# temp-stellwerk-laser-4.net
KiCad netlist of a schematic drawn in EAGLE
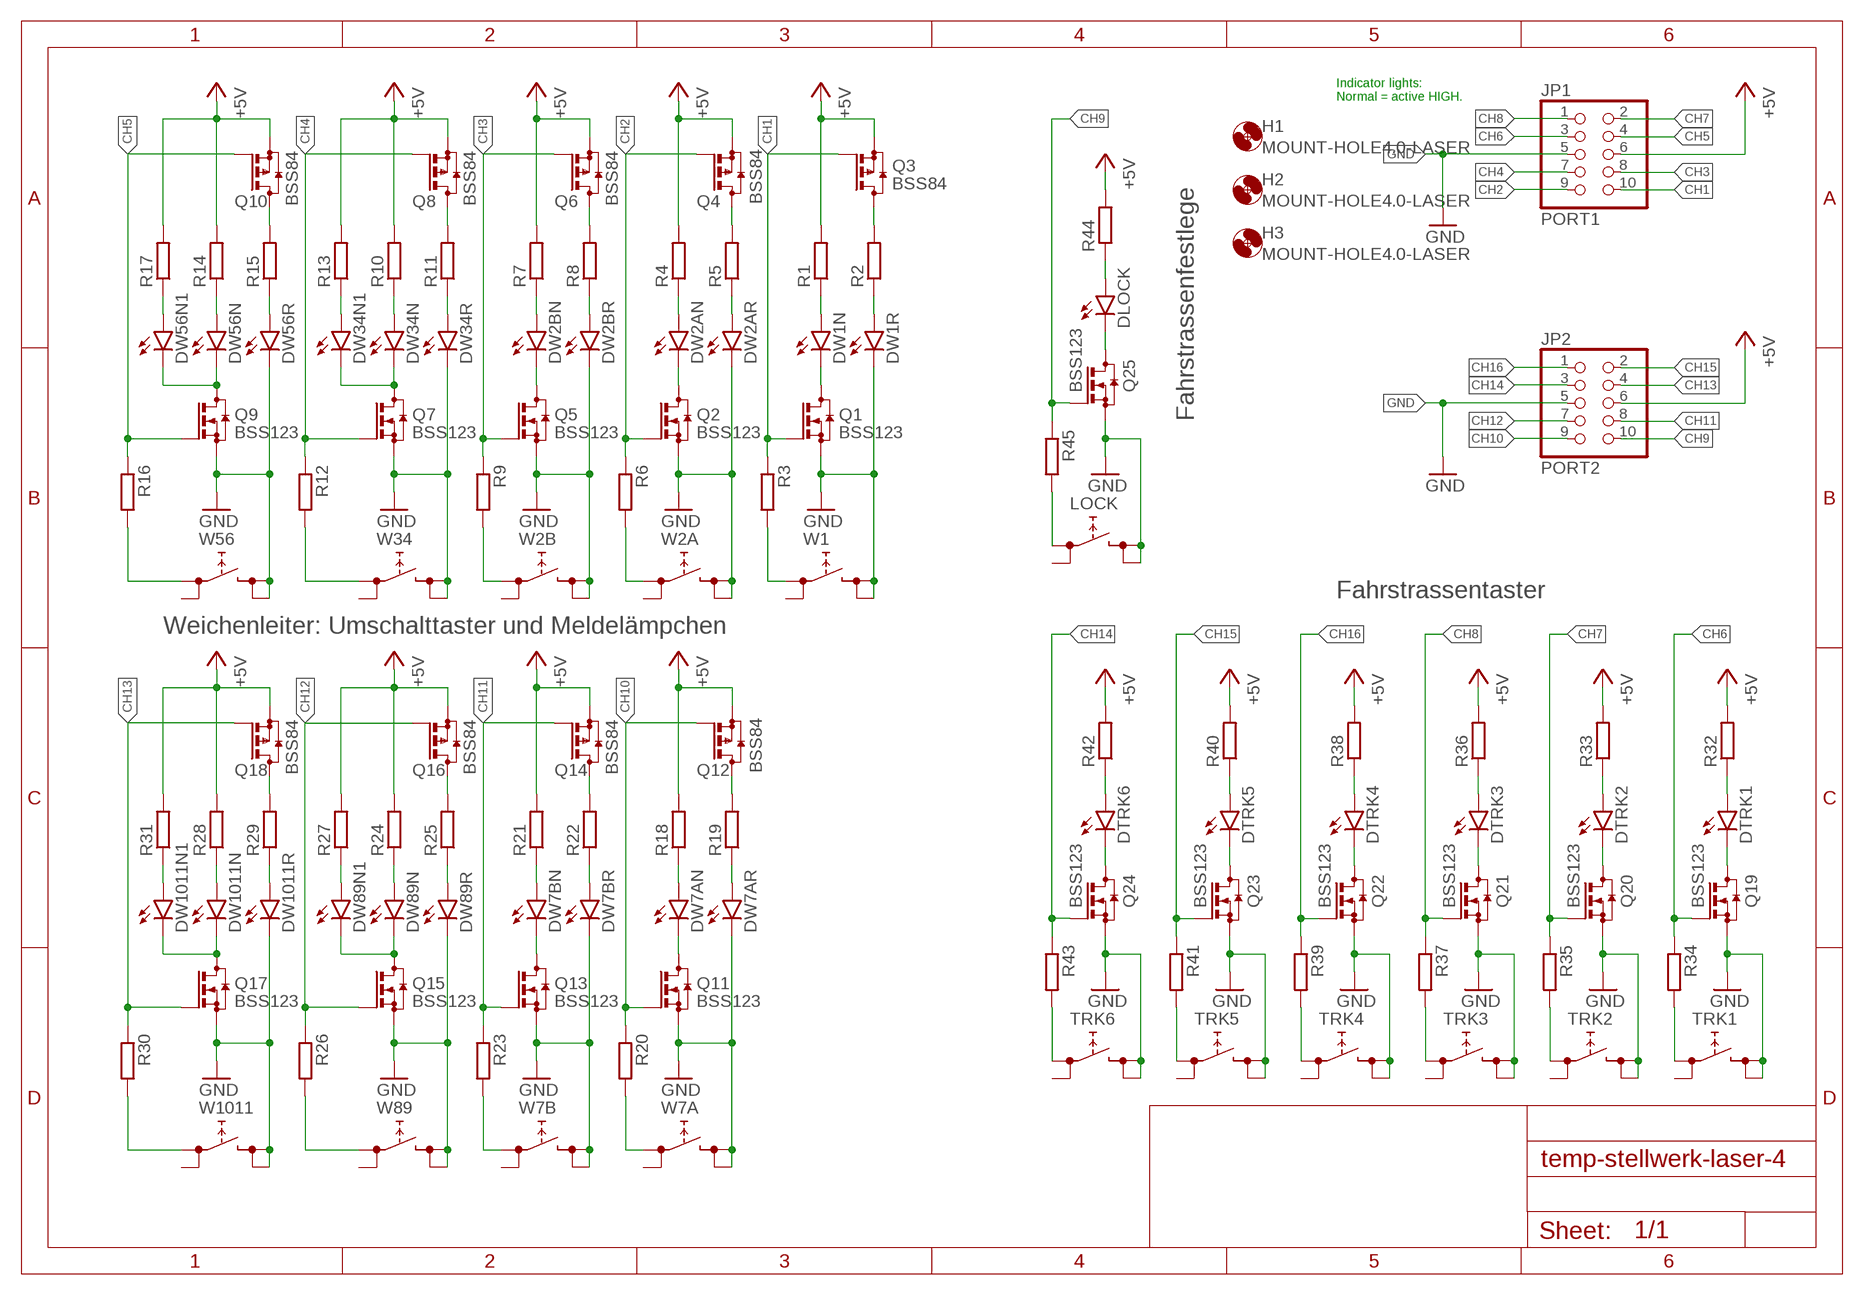
[diagram p0: schematic, sheet 1]

(export (version "E")
  (design (tool "Eeschema 10.0.6"))
  (components
    (comp (ref "DLOCK")
      (value "LEDCHIPLED_0805")
      (footprint "eagle-import:CHIPLED_0805")
      (libsource (lib "eagle-import") (part "LEDCHIPLED_0805"))
    )
    (comp (ref "DTRK1")
      (value "LEDCHIPLED_0805")
      (footprint "eagle-import:CHIPLED_0805")
      (libsource (lib "eagle-import") (part "LEDCHIPLED_0805"))
    )
    (comp (ref "DTRK2")
      (value "LEDCHIPLED_0805")
      (footprint "eagle-import:CHIPLED_0805")
      (libsource (lib "eagle-import") (part "LEDCHIPLED_0805"))
    )
    (comp (ref "DTRK3")
      (value "LEDCHIPLED_0805")
      (footprint "eagle-import:CHIPLED_0805")
      (libsource (lib "eagle-import") (part "LEDCHIPLED_0805"))
    )
    (comp (ref "DTRK4")
      (value "LEDCHIPLED_0805")
      (footprint "eagle-import:CHIPLED_0805")
      (libsource (lib "eagle-import") (part "LEDCHIPLED_0805"))
    )
    (comp (ref "DTRK5")
      (value "LEDCHIPLED_0805")
      (footprint "eagle-import:CHIPLED_0805")
      (libsource (lib "eagle-import") (part "LEDCHIPLED_0805"))
    )
    (comp (ref "DTRK6")
      (value "LEDCHIPLED_0805")
      (footprint "eagle-import:CHIPLED_0805")
      (libsource (lib "eagle-import") (part "LEDCHIPLED_0805"))
    )
    (comp (ref "DW1N")
      (value "LEDCHIPLED_0603")
      (footprint "eagle-import:CHIPLED_0603")
      (libsource (lib "eagle-import") (part "LEDCHIPLED_0603"))
    )
    (comp (ref "DW1R")
      (value "LEDCHIPLED_0603")
      (footprint "eagle-import:CHIPLED_0603")
      (libsource (lib "eagle-import") (part "LEDCHIPLED_0603"))
    )
    (comp (ref "DW2AN")
      (value "LEDCHIPLED_0603")
      (footprint "eagle-import:CHIPLED_0603")
      (libsource (lib "eagle-import") (part "LEDCHIPLED_0603"))
    )
    (comp (ref "DW2AR")
      (value "LEDCHIPLED_0603")
      (footprint "eagle-import:CHIPLED_0603")
      (libsource (lib "eagle-import") (part "LEDCHIPLED_0603"))
    )
    (comp (ref "DW2BN")
      (value "LEDCHIPLED_0805")
      (footprint "eagle-import:CHIPLED_0805")
      (libsource (lib "eagle-import") (part "LEDCHIPLED_0805"))
    )
    (comp (ref "DW2BR")
      (value "LEDCHIPLED_0805")
      (footprint "eagle-import:CHIPLED_0805")
      (libsource (lib "eagle-import") (part "LEDCHIPLED_0805"))
    )
    (comp (ref "DW7AN")
      (value "LEDCHIPLED_0603")
      (footprint "eagle-import:CHIPLED_0603")
      (libsource (lib "eagle-import") (part "LEDCHIPLED_0603"))
    )
    (comp (ref "DW7AR")
      (value "LEDCHIPLED_0603")
      (footprint "eagle-import:CHIPLED_0603")
      (libsource (lib "eagle-import") (part "LEDCHIPLED_0603"))
    )
    (comp (ref "DW7BN")
      (value "LEDCHIPLED_0805")
      (footprint "eagle-import:CHIPLED_0805")
      (libsource (lib "eagle-import") (part "LEDCHIPLED_0805"))
    )
    (comp (ref "DW7BR")
      (value "LEDCHIPLED_0805")
      (footprint "eagle-import:CHIPLED_0805")
      (libsource (lib "eagle-import") (part "LEDCHIPLED_0805"))
    )
    (comp (ref "DW34N")
      (value "LEDCHIPLED_0805")
      (footprint "eagle-import:CHIPLED_0805")
      (libsource (lib "eagle-import") (part "LEDCHIPLED_0805"))
    )
    (comp (ref "DW34N1")
      (value "LEDCHIPLED_0805")
      (footprint "eagle-import:CHIPLED_0805")
      (libsource (lib "eagle-import") (part "LEDCHIPLED_0805"))
    )
    (comp (ref "DW34R")
      (value "LEDCHIPLED_0805")
      (footprint "eagle-import:CHIPLED_0805")
      (libsource (lib "eagle-import") (part "LEDCHIPLED_0805"))
    )
    (comp (ref "DW56N")
      (value "LEDCHIPLED_0805")
      (footprint "eagle-import:CHIPLED_0805")
      (libsource (lib "eagle-import") (part "LEDCHIPLED_0805"))
    )
    (comp (ref "DW56N1")
      (value "LEDCHIPLED_0805")
      (footprint "eagle-import:CHIPLED_0805")
      (libsource (lib "eagle-import") (part "LEDCHIPLED_0805"))
    )
    (comp (ref "DW56R")
      (value "LEDCHIPLED_0805")
      (footprint "eagle-import:CHIPLED_0805")
      (libsource (lib "eagle-import") (part "LEDCHIPLED_0805"))
    )
    (comp (ref "DW89N")
      (value "LEDCHIPLED_0805")
      (footprint "eagle-import:CHIPLED_0805")
      (libsource (lib "eagle-import") (part "LEDCHIPLED_0805"))
    )
    (comp (ref "DW89N1")
      (value "LEDCHIPLED_0805")
      (footprint "eagle-import:CHIPLED_0805")
      (libsource (lib "eagle-import") (part "LEDCHIPLED_0805"))
    )
    (comp (ref "DW89R")
      (value "LEDCHIPLED_0805")
      (footprint "eagle-import:CHIPLED_0805")
      (libsource (lib "eagle-import") (part "LEDCHIPLED_0805"))
    )
    (comp (ref "DW1011N")
      (value "LEDCHIPLED_0805")
      (footprint "eagle-import:CHIPLED_0805")
      (libsource (lib "eagle-import") (part "LEDCHIPLED_0805"))
    )
    (comp (ref "DW1011N1")
      (value "LEDCHIPLED_0805")
      (footprint "eagle-import:CHIPLED_0805")
      (libsource (lib "eagle-import") (part "LEDCHIPLED_0805"))
    )
    (comp (ref "DW1011R")
      (value "LEDCHIPLED_0805")
      (footprint "eagle-import:CHIPLED_0805")
      (libsource (lib "eagle-import") (part "LEDCHIPLED_0805"))
    )
    (comp (ref "H1")
      (value "MOUNT-HOLE4.0-LASER")
      (footprint "eagle-import:MOUNT-HOLE-3.2-4.0-LASER")
      (libsource (lib "eagle-import") (part "MOUNT-HOLE4.0-LASER"))
    )
    (comp (ref "H2")
      (value "MOUNT-HOLE4.0-LASER")
      (footprint "eagle-import:MOUNT-HOLE-3.2-4.0-LASER")
      (libsource (lib "eagle-import") (part "MOUNT-HOLE4.0-LASER"))
    )
    (comp (ref "H3")
      (value "MOUNT-HOLE4.0-LASER")
      (footprint "eagle-import:MOUNT-HOLE-3.2-4.0-LASER")
      (libsource (lib "eagle-import") (part "MOUNT-HOLE4.0-LASER"))
    )
    (comp (ref "JP1")
      (value "PORT1")
      (footprint "eagle-import:CON10M")
      (libsource (lib "eagle-import") (part "PINHD-2X5CN"))
    )
    (comp (ref "JP2")
      (value "PORT2")
      (footprint "eagle-import:CON10M")
      (libsource (lib "eagle-import") (part "PINHD-2X5CN"))
    )
    (comp (ref "LOCK")
      (value "LOCK")
      (footprint "eagle-import:TACTSW-6X6-LASER")
      (libsource (lib "eagle-import") (part "TACTSW-6X6S"))
    )
    (comp (ref "Q1")
      (value "BSS123")
      (footprint "eagle-import:SOT23-NCH")
      (libsource (lib "eagle-import") (part "BSS123"))
    )
    (comp (ref "Q2")
      (value "BSS123")
      (footprint "eagle-import:SOT23-NCH")
      (libsource (lib "eagle-import") (part "BSS123"))
    )
    (comp (ref "Q3")
      (value "BSS84")
      (footprint "eagle-import:SOT23")
      (libsource (lib "eagle-import") (part "BSS84"))
    )
    (comp (ref "Q4")
      (value "BSS84")
      (footprint "eagle-import:SOT23")
      (libsource (lib "eagle-import") (part "BSS84"))
    )
    (comp (ref "Q5")
      (value "BSS123")
      (footprint "eagle-import:SOT23-NCH")
      (libsource (lib "eagle-import") (part "BSS123"))
    )
    (comp (ref "Q6")
      (value "BSS84")
      (footprint "eagle-import:SOT23")
      (libsource (lib "eagle-import") (part "BSS84"))
    )
    (comp (ref "Q7")
      (value "BSS123")
      (footprint "eagle-import:SOT23-NCH")
      (libsource (lib "eagle-import") (part "BSS123"))
    )
    (comp (ref "Q8")
      (value "BSS84")
      (footprint "eagle-import:SOT23")
      (libsource (lib "eagle-import") (part "BSS84"))
    )
    (comp (ref "Q9")
      (value "BSS123")
      (footprint "eagle-import:SOT23-NCH")
      (libsource (lib "eagle-import") (part "BSS123"))
    )
    (comp (ref "Q10")
      (value "BSS84")
      (footprint "eagle-import:SOT23")
      (libsource (lib "eagle-import") (part "BSS84"))
    )
    (comp (ref "Q11")
      (value "BSS123")
      (footprint "eagle-import:SOT23-NCH")
      (libsource (lib "eagle-import") (part "BSS123"))
    )
    (comp (ref "Q12")
      (value "BSS84")
      (footprint "eagle-import:SOT23")
      (libsource (lib "eagle-import") (part "BSS84"))
    )
    (comp (ref "Q13")
      (value "BSS123")
      (footprint "eagle-import:SOT23-NCH")
      (libsource (lib "eagle-import") (part "BSS123"))
    )
    (comp (ref "Q14")
      (value "BSS84")
      (footprint "eagle-import:SOT23")
      (libsource (lib "eagle-import") (part "BSS84"))
    )
    (comp (ref "Q15")
      (value "BSS123")
      (footprint "eagle-import:SOT23-NCH")
      (libsource (lib "eagle-import") (part "BSS123"))
    )
    (comp (ref "Q16")
      (value "BSS84")
      (footprint "eagle-import:SOT23")
      (libsource (lib "eagle-import") (part "BSS84"))
    )
    (comp (ref "Q17")
      (value "BSS123")
      (footprint "eagle-import:SOT23-NCH")
      (libsource (lib "eagle-import") (part "BSS123"))
    )
    (comp (ref "Q18")
      (value "BSS84")
      (footprint "eagle-import:SOT23")
      (libsource (lib "eagle-import") (part "BSS84"))
    )
    (comp (ref "Q19")
      (value "BSS123")
      (footprint "eagle-import:SOT23-NCH")
      (libsource (lib "eagle-import") (part "BSS123"))
    )
    (comp (ref "Q20")
      (value "BSS123")
      (footprint "eagle-import:SOT23-NCH")
      (libsource (lib "eagle-import") (part "BSS123"))
    )
    (comp (ref "Q21")
      (value "BSS123")
      (footprint "eagle-import:SOT23-NCH")
      (libsource (lib "eagle-import") (part "BSS123"))
    )
    (comp (ref "Q22")
      (value "BSS123")
      (footprint "eagle-import:SOT23-NCH")
      (libsource (lib "eagle-import") (part "BSS123"))
    )
    (comp (ref "Q23")
      (value "BSS123")
      (footprint "eagle-import:SOT23-NCH")
      (libsource (lib "eagle-import") (part "BSS123"))
    )
    (comp (ref "Q24")
      (value "BSS123")
      (footprint "eagle-import:SOT23-NCH")
      (libsource (lib "eagle-import") (part "BSS123"))
    )
    (comp (ref "Q25")
      (value "BSS123")
      (footprint "eagle-import:SOT23-NCH")
      (libsource (lib "eagle-import") (part "BSS123"))
    )
    (comp (ref "R1")
      (value "R-EU_R0805")
      (footprint "eagle-import:R0805")
      (libsource (lib "eagle-import") (part "R-EU_R0805"))
    )
    (comp (ref "R2")
      (value "R-EU_R0805")
      (footprint "eagle-import:R0805")
      (libsource (lib "eagle-import") (part "R-EU_R0805"))
    )
    (comp (ref "R3")
      (value "R-EU_R0805")
      (footprint "eagle-import:R0805")
      (libsource (lib "eagle-import") (part "R-EU_R0805"))
    )
    (comp (ref "R4")
      (value "R-EU_R0805")
      (footprint "eagle-import:R0805")
      (libsource (lib "eagle-import") (part "R-EU_R0805"))
    )
    (comp (ref "R5")
      (value "R-EU_R0805")
      (footprint "eagle-import:R0805")
      (libsource (lib "eagle-import") (part "R-EU_R0805"))
    )
    (comp (ref "R6")
      (value "R-EU_R0805")
      (footprint "eagle-import:R0805")
      (libsource (lib "eagle-import") (part "R-EU_R0805"))
    )
    (comp (ref "R7")
      (value "R-EU_R0805")
      (footprint "eagle-import:R0805")
      (libsource (lib "eagle-import") (part "R-EU_R0805"))
    )
    (comp (ref "R8")
      (value "R-EU_R0805")
      (footprint "eagle-import:R0805")
      (libsource (lib "eagle-import") (part "R-EU_R0805"))
    )
    (comp (ref "R9")
      (value "R-EU_R0805")
      (footprint "eagle-import:R0805")
      (libsource (lib "eagle-import") (part "R-EU_R0805"))
    )
    (comp (ref "R10")
      (value "R-EU_R0805")
      (footprint "eagle-import:R0805")
      (libsource (lib "eagle-import") (part "R-EU_R0805"))
    )
    (comp (ref "R11")
      (value "R-EU_R0805")
      (footprint "eagle-import:R0805")
      (libsource (lib "eagle-import") (part "R-EU_R0805"))
    )
    (comp (ref "R12")
      (value "R-EU_R0805")
      (footprint "eagle-import:R0805")
      (libsource (lib "eagle-import") (part "R-EU_R0805"))
    )
    (comp (ref "R13")
      (value "R-EU_R0805")
      (footprint "eagle-import:R0805")
      (libsource (lib "eagle-import") (part "R-EU_R0805"))
    )
    (comp (ref "R14")
      (value "R-EU_R0805")
      (footprint "eagle-import:R0805")
      (libsource (lib "eagle-import") (part "R-EU_R0805"))
    )
    (comp (ref "R15")
      (value "R-EU_R0805")
      (footprint "eagle-import:R0805")
      (libsource (lib "eagle-import") (part "R-EU_R0805"))
    )
    (comp (ref "R16")
      (value "R-EU_R0805")
      (footprint "eagle-import:R0805")
      (libsource (lib "eagle-import") (part "R-EU_R0805"))
    )
    (comp (ref "R17")
      (value "R-EU_R0805")
      (footprint "eagle-import:R0805")
      (libsource (lib "eagle-import") (part "R-EU_R0805"))
    )
    (comp (ref "R18")
      (value "R-EU_R0805")
      (footprint "eagle-import:R0805")
      (libsource (lib "eagle-import") (part "R-EU_R0805"))
    )
    (comp (ref "R19")
      (value "R-EU_R0805")
      (footprint "eagle-import:R0805")
      (libsource (lib "eagle-import") (part "R-EU_R0805"))
    )
    (comp (ref "R20")
      (value "R-EU_R0805")
      (footprint "eagle-import:R0805")
      (libsource (lib "eagle-import") (part "R-EU_R0805"))
    )
    (comp (ref "R21")
      (value "R-EU_R0805")
      (footprint "eagle-import:R0805")
      (libsource (lib "eagle-import") (part "R-EU_R0805"))
    )
    (comp (ref "R22")
      (value "R-EU_R0805")
      (footprint "eagle-import:R0805")
      (libsource (lib "eagle-import") (part "R-EU_R0805"))
    )
    (comp (ref "R23")
      (value "R-EU_R0805")
      (footprint "eagle-import:R0805")
      (libsource (lib "eagle-import") (part "R-EU_R0805"))
    )
    (comp (ref "R24")
      (value "R-EU_R0805")
      (footprint "eagle-import:R0805")
      (libsource (lib "eagle-import") (part "R-EU_R0805"))
    )
    (comp (ref "R25")
      (value "R-EU_R0805")
      (footprint "eagle-import:R0805")
      (libsource (lib "eagle-import") (part "R-EU_R0805"))
    )
    (comp (ref "R26")
      (value "R-EU_R0805")
      (footprint "eagle-import:R0805")
      (libsource (lib "eagle-import") (part "R-EU_R0805"))
    )
    (comp (ref "R27")
      (value "R-EU_R0805")
      (footprint "eagle-import:R0805")
      (libsource (lib "eagle-import") (part "R-EU_R0805"))
    )
    (comp (ref "R28")
      (value "R-EU_R0805")
      (footprint "eagle-import:R0805")
      (libsource (lib "eagle-import") (part "R-EU_R0805"))
    )
    (comp (ref "R29")
      (value "R-EU_R0805")
      (footprint "eagle-import:R0805")
      (libsource (lib "eagle-import") (part "R-EU_R0805"))
    )
    (comp (ref "R30")
      (value "R-EU_R0805")
      (footprint "eagle-import:R0805")
      (libsource (lib "eagle-import") (part "R-EU_R0805"))
    )
    (comp (ref "R31")
      (value "R-EU_R0805")
      (footprint "eagle-import:R0805")
      (libsource (lib "eagle-import") (part "R-EU_R0805"))
    )
    (comp (ref "R32")
      (value "R-EU_R0805")
      (footprint "eagle-import:R0805")
      (libsource (lib "eagle-import") (part "R-EU_R0805"))
    )
    (comp (ref "R33")
      (value "R-EU_R0805")
      (footprint "eagle-import:R0805")
      (libsource (lib "eagle-import") (part "R-EU_R0805"))
    )
    (comp (ref "R34")
      (value "R-EU_R0805")
      (footprint "eagle-import:R0805")
      (libsource (lib "eagle-import") (part "R-EU_R0805"))
    )
    (comp (ref "R35")
      (value "R-EU_R0805")
      (footprint "eagle-import:R0805")
      (libsource (lib "eagle-import") (part "R-EU_R0805"))
    )
    (comp (ref "R36")
      (value "R-EU_R0805")
      (footprint "eagle-import:R0805")
      (libsource (lib "eagle-import") (part "R-EU_R0805"))
    )
    (comp (ref "R37")
      (value "R-EU_R0805")
      (footprint "eagle-import:R0805")
      (libsource (lib "eagle-import") (part "R-EU_R0805"))
    )
    (comp (ref "R38")
      (value "R-EU_R0805")
      (footprint "eagle-import:R0805")
      (libsource (lib "eagle-import") (part "R-EU_R0805"))
    )
    (comp (ref "R39")
      (value "R-EU_R0805")
      (footprint "eagle-import:R0805")
      (libsource (lib "eagle-import") (part "R-EU_R0805"))
    )
    (comp (ref "R40")
      (value "R-EU_R0805")
      (footprint "eagle-import:R0805")
      (libsource (lib "eagle-import") (part "R-EU_R0805"))
    )
    (comp (ref "R41")
      (value "R-EU_R0805")
      (footprint "eagle-import:R0805")
      (libsource (lib "eagle-import") (part "R-EU_R0805"))
    )
    (comp (ref "R42")
      (value "R-EU_R0805")
      (footprint "eagle-import:R0805")
      (libsource (lib "eagle-import") (part "R-EU_R0805"))
    )
    (comp (ref "R43")
      (value "R-EU_R0805")
      (footprint "eagle-import:R0805")
      (libsource (lib "eagle-import") (part "R-EU_R0805"))
    )
    (comp (ref "R44")
      (value "R-EU_R0805")
      (footprint "eagle-import:R0805")
      (libsource (lib "eagle-import") (part "R-EU_R0805"))
    )
    (comp (ref "R45")
      (value "R-EU_R0805")
      (footprint "eagle-import:R0805")
      (libsource (lib "eagle-import") (part "R-EU_R0805"))
    )
    (comp (ref "TRK1")
      (value "TACTSW-6X6S")
      (footprint "eagle-import:TACTSW-6X6-LASER")
      (libsource (lib "eagle-import") (part "TACTSW-6X6S"))
    )
    (comp (ref "TRK2")
      (value "TACTSW-6X6S")
      (footprint "eagle-import:TACTSW-6X6-LASER")
      (libsource (lib "eagle-import") (part "TACTSW-6X6S"))
    )
    (comp (ref "TRK3")
      (value "TACTSW-6X6S")
      (footprint "eagle-import:TACTSW-6X6-LASER")
      (libsource (lib "eagle-import") (part "TACTSW-6X6S"))
    )
    (comp (ref "TRK4")
      (value "TACTSW-6X6S")
      (footprint "eagle-import:TACTSW-6X6-LASER")
      (libsource (lib "eagle-import") (part "TACTSW-6X6S"))
    )
    (comp (ref "TRK5")
      (value "TACTSW-6X6S")
      (footprint "eagle-import:TACTSW-6X6-LASER")
      (libsource (lib "eagle-import") (part "TACTSW-6X6S"))
    )
    (comp (ref "TRK6")
      (value "TACTSW-6X6S")
      (footprint "eagle-import:TACTSW-6X6-LASER")
      (libsource (lib "eagle-import") (part "TACTSW-6X6S"))
    )
    (comp (ref "W1")
      (value "W1")
      (footprint "eagle-import:TACTSW-6X6-LASER")
      (libsource (lib "eagle-import") (part "TACTSW-6X6S"))
    )
    (comp (ref "W2A")
      (value "TACTSW-6X6S")
      (footprint "eagle-import:TACTSW-6X6-LASER")
      (libsource (lib "eagle-import") (part "TACTSW-6X6S"))
    )
    (comp (ref "W2B")
      (value "TACTSW-6X6S")
      (footprint "eagle-import:TACTSW-6X6-LASER")
      (libsource (lib "eagle-import") (part "TACTSW-6X6S"))
    )
    (comp (ref "W7A")
      (value "TACTSW-6X6S")
      (footprint "eagle-import:TACTSW-6X6-LASER")
      (libsource (lib "eagle-import") (part "TACTSW-6X6S"))
    )
    (comp (ref "W7B")
      (value "TACTSW-6X6S")
      (footprint "eagle-import:TACTSW-6X6-LASER")
      (libsource (lib "eagle-import") (part "TACTSW-6X6S"))
    )
    (comp (ref "W34")
      (value "XOVER")
      (footprint "eagle-import:TACTSW-6X6-LASER")
      (libsource (lib "eagle-import") (part "TACTSW-6X6S"))
    )
    (comp (ref "W56")
      (value "XOVER")
      (footprint "eagle-import:TACTSW-6X6-LASER")
      (libsource (lib "eagle-import") (part "TACTSW-6X6S"))
    )
    (comp (ref "W89")
      (value "XOVER")
      (footprint "eagle-import:TACTSW-6X6-LASER")
      (libsource (lib "eagle-import") (part "TACTSW-6X6S"))
    )
    (comp (ref "W1011")
      (value "XOVER")
      (footprint "eagle-import:TACTSW-6X6-LASER")
      (libsource (lib "eagle-import") (part "TACTSW-6X6S"))
    )
  )
  (nets
    (net (code "1") (name "+5V") (class "Default")
      (node (ref "JP1") (pin "6") (pinfunction "6_6") (pintype "passive"))
      (node (ref "JP2") (pin "6") (pinfunction "6_6") (pintype "passive"))
      (node (ref "Q10") (pin "2") (pinfunction "S_2") (pintype "passive"))
      (node (ref "Q12") (pin "2") (pinfunction "S_2") (pintype "passive"))
      (node (ref "Q14") (pin "2") (pinfunction "S_2") (pintype "passive"))
      (node (ref "Q16") (pin "2") (pinfunction "S_2") (pintype "passive"))
      (node (ref "Q18") (pin "2") (pinfunction "S_2") (pintype "passive"))
      (node (ref "Q3") (pin "2") (pinfunction "S_2") (pintype "passive"))
      (node (ref "Q4") (pin "2") (pinfunction "S_2") (pintype "passive"))
      (node (ref "Q6") (pin "2") (pinfunction "S_2") (pintype "passive"))
      (node (ref "Q8") (pin "2") (pinfunction "S_2") (pintype "passive"))
      (node (ref "R1") (pin "2") (pinfunction "2_2") (pintype "passive"))
      (node (ref "R10") (pin "2") (pinfunction "2_2") (pintype "passive"))
      (node (ref "R13") (pin "2") (pinfunction "2_2") (pintype "passive"))
      (node (ref "R14") (pin "2") (pinfunction "2_2") (pintype "passive"))
      (node (ref "R17") (pin "2") (pinfunction "2_2") (pintype "passive"))
      (node (ref "R18") (pin "2") (pinfunction "2_2") (pintype "passive"))
      (node (ref "R21") (pin "2") (pinfunction "2_2") (pintype "passive"))
      (node (ref "R24") (pin "2") (pinfunction "2_2") (pintype "passive"))
      (node (ref "R27") (pin "2") (pinfunction "2_2") (pintype "passive"))
      (node (ref "R28") (pin "2") (pinfunction "2_2") (pintype "passive"))
      (node (ref "R31") (pin "2") (pinfunction "2_2") (pintype "passive"))
      (node (ref "R32") (pin "2") (pinfunction "2_2") (pintype "passive"))
      (node (ref "R33") (pin "2") (pinfunction "2_2") (pintype "passive"))
      (node (ref "R36") (pin "2") (pinfunction "2_2") (pintype "passive"))
      (node (ref "R38") (pin "2") (pinfunction "2_2") (pintype "passive"))
      (node (ref "R4") (pin "2") (pinfunction "2_2") (pintype "passive"))
      (node (ref "R40") (pin "2") (pinfunction "2_2") (pintype "passive"))
      (node (ref "R42") (pin "2") (pinfunction "2_2") (pintype "passive"))
      (node (ref "R44") (pin "2") (pinfunction "2_2") (pintype "passive"))
      (node (ref "R7") (pin "2") (pinfunction "2_2") (pintype "passive"))
    )
    (net (code "2") (name "CH1") (class "Default")
      (node (ref "JP1") (pin "10") (pinfunction "10_10") (pintype "passive"))
      (node (ref "Q1") (pin "1") (pinfunction "G_1") (pintype "passive"))
      (node (ref "Q3") (pin "1") (pinfunction "G_1") (pintype "passive"))
      (node (ref "R3") (pin "1") (pinfunction "1_1") (pintype "passive"))
    )
    (net (code "3") (name "CH2") (class "Default")
      (node (ref "JP1") (pin "9") (pinfunction "9_9") (pintype "passive"))
      (node (ref "Q2") (pin "1") (pinfunction "G_1") (pintype "passive"))
      (node (ref "Q4") (pin "1") (pinfunction "G_1") (pintype "passive"))
      (node (ref "R6") (pin "1") (pinfunction "1_1") (pintype "passive"))
    )
    (net (code "4") (name "CH3") (class "Default")
      (node (ref "JP1") (pin "8") (pinfunction "8_8") (pintype "passive"))
      (node (ref "Q5") (pin "1") (pinfunction "G_1") (pintype "passive"))
      (node (ref "Q6") (pin "1") (pinfunction "G_1") (pintype "passive"))
      (node (ref "R9") (pin "1") (pinfunction "1_1") (pintype "passive"))
    )
    (net (code "5") (name "CH4") (class "Default")
      (node (ref "JP1") (pin "7") (pinfunction "7_7") (pintype "passive"))
      (node (ref "Q7") (pin "1") (pinfunction "G_1") (pintype "passive"))
      (node (ref "Q8") (pin "1") (pinfunction "G_1") (pintype "passive"))
      (node (ref "R12") (pin "1") (pinfunction "1_1") (pintype "passive"))
    )
    (net (code "6") (name "CH5") (class "Default")
      (node (ref "JP1") (pin "4") (pinfunction "4_4") (pintype "passive"))
      (node (ref "Q10") (pin "1") (pinfunction "G_1") (pintype "passive"))
      (node (ref "Q9") (pin "1") (pinfunction "G_1") (pintype "passive"))
      (node (ref "R16") (pin "1") (pinfunction "1_1") (pintype "passive"))
    )
    (net (code "7") (name "CH6") (class "Default")
      (node (ref "JP1") (pin "3") (pinfunction "3_3") (pintype "passive"))
      (node (ref "Q19") (pin "1") (pinfunction "G_1") (pintype "passive"))
      (node (ref "R34") (pin "1") (pinfunction "1_1") (pintype "passive"))
    )
    (net (code "8") (name "CH7") (class "Default")
      (node (ref "JP1") (pin "2") (pinfunction "2_2") (pintype "passive"))
      (node (ref "Q20") (pin "1") (pinfunction "G_1") (pintype "passive"))
      (node (ref "R35") (pin "1") (pinfunction "1_1") (pintype "passive"))
    )
    (net (code "9") (name "CH8") (class "Default")
      (node (ref "JP1") (pin "1") (pinfunction "1_1") (pintype "passive"))
      (node (ref "Q21") (pin "1") (pinfunction "G_1") (pintype "passive"))
      (node (ref "R37") (pin "1") (pinfunction "1_1") (pintype "passive"))
    )
    (net (code "10") (name "CH9") (class "Default")
      (node (ref "JP2") (pin "10") (pinfunction "10_10") (pintype "passive"))
      (node (ref "Q25") (pin "1") (pinfunction "G_1") (pintype "passive"))
      (node (ref "R45") (pin "1") (pinfunction "1_1") (pintype "passive"))
    )
    (net (code "11") (name "CH10") (class "Default")
      (node (ref "JP2") (pin "9") (pinfunction "9_9") (pintype "passive"))
      (node (ref "Q11") (pin "1") (pinfunction "G_1") (pintype "passive"))
      (node (ref "Q12") (pin "1") (pinfunction "G_1") (pintype "passive"))
      (node (ref "R20") (pin "1") (pinfunction "1_1") (pintype "passive"))
    )
    (net (code "12") (name "CH11") (class "Default")
      (node (ref "JP2") (pin "8") (pinfunction "8_8") (pintype "passive"))
      (node (ref "Q13") (pin "1") (pinfunction "G_1") (pintype "passive"))
      (node (ref "Q14") (pin "1") (pinfunction "G_1") (pintype "passive"))
      (node (ref "R23") (pin "1") (pinfunction "1_1") (pintype "passive"))
    )
    (net (code "13") (name "CH12") (class "Default")
      (node (ref "JP2") (pin "7") (pinfunction "7_7") (pintype "passive"))
      (node (ref "Q15") (pin "1") (pinfunction "G_1") (pintype "passive"))
      (node (ref "Q16") (pin "1") (pinfunction "G_1") (pintype "passive"))
      (node (ref "R26") (pin "1") (pinfunction "1_1") (pintype "passive"))
    )
    (net (code "14") (name "CH13") (class "Default")
      (node (ref "JP2") (pin "4") (pinfunction "4_4") (pintype "passive"))
      (node (ref "Q17") (pin "1") (pinfunction "G_1") (pintype "passive"))
      (node (ref "Q18") (pin "1") (pinfunction "G_1") (pintype "passive"))
      (node (ref "R30") (pin "1") (pinfunction "1_1") (pintype "passive"))
    )
    (net (code "15") (name "CH14") (class "Default")
      (node (ref "JP2") (pin "3") (pinfunction "3_3") (pintype "passive"))
      (node (ref "Q24") (pin "1") (pinfunction "G_1") (pintype "passive"))
      (node (ref "R43") (pin "1") (pinfunction "1_1") (pintype "passive"))
    )
    (net (code "16") (name "CH15") (class "Default")
      (node (ref "JP2") (pin "2") (pinfunction "2_2") (pintype "passive"))
      (node (ref "Q23") (pin "1") (pinfunction "G_1") (pintype "passive"))
      (node (ref "R41") (pin "1") (pinfunction "1_1") (pintype "passive"))
    )
    (net (code "17") (name "CH16") (class "Default")
      (node (ref "JP2") (pin "1") (pinfunction "1_1") (pintype "passive"))
      (node (ref "Q22") (pin "1") (pinfunction "G_1") (pintype "passive"))
      (node (ref "R39") (pin "1") (pinfunction "1_1") (pintype "passive"))
    )
    (net (code "18") (name "GND") (class "Default")
      (node (ref "DW1011R") (pin "C") (pinfunction "C_C") (pintype "passive"))
      (node (ref "DW1R") (pin "C") (pinfunction "C_C") (pintype "passive"))
      (node (ref "DW2AR") (pin "C") (pinfunction "C_C") (pintype "passive"))
      (node (ref "DW2BR") (pin "C") (pinfunction "C_C") (pintype "passive"))
      (node (ref "DW34R") (pin "C") (pinfunction "C_C") (pintype "passive"))
      (node (ref "DW56R") (pin "C") (pinfunction "C_C") (pintype "passive"))
      (node (ref "DW7AR") (pin "C") (pinfunction "C_C") (pintype "passive"))
      (node (ref "DW7BR") (pin "C") (pinfunction "C_C") (pintype "passive"))
      (node (ref "DW89R") (pin "C") (pinfunction "C_C") (pintype "passive"))
      (node (ref "JP1") (pin "5") (pinfunction "5_5") (pintype "passive"))
      (node (ref "JP2") (pin "5") (pinfunction "5_5") (pintype "passive"))
      (node (ref "LOCK") (pin "3") (pinfunction "2.1_3") (pintype "passive"))
      (node (ref "LOCK") (pin "4") (pinfunction "2.2_4") (pintype "passive"))
      (node (ref "Q1") (pin "2") (pinfunction "S_2") (pintype "passive"))
      (node (ref "Q11") (pin "2") (pinfunction "S_2") (pintype "passive"))
      (node (ref "Q13") (pin "2") (pinfunction "S_2") (pintype "passive"))
      (node (ref "Q15") (pin "2") (pinfunction "S_2") (pintype "passive"))
      (node (ref "Q17") (pin "2") (pinfunction "S_2") (pintype "passive"))
      (node (ref "Q19") (pin "2") (pinfunction "S_2") (pintype "passive"))
      (node (ref "Q2") (pin "2") (pinfunction "S_2") (pintype "passive"))
      (node (ref "Q20") (pin "2") (pinfunction "S_2") (pintype "passive"))
      (node (ref "Q21") (pin "2") (pinfunction "S_2") (pintype "passive"))
      (node (ref "Q22") (pin "2") (pinfunction "S_2") (pintype "passive"))
      (node (ref "Q23") (pin "2") (pinfunction "S_2") (pintype "passive"))
      (node (ref "Q24") (pin "2") (pinfunction "S_2") (pintype "passive"))
      (node (ref "Q25") (pin "2") (pinfunction "S_2") (pintype "passive"))
      (node (ref "Q5") (pin "2") (pinfunction "S_2") (pintype "passive"))
      (node (ref "Q7") (pin "2") (pinfunction "S_2") (pintype "passive"))
      (node (ref "Q9") (pin "2") (pinfunction "S_2") (pintype "passive"))
      (node (ref "TRK1") (pin "3") (pinfunction "2.1_3") (pintype "passive"))
      (node (ref "TRK1") (pin "4") (pinfunction "2.2_4") (pintype "passive"))
      (node (ref "TRK2") (pin "3") (pinfunction "2.1_3") (pintype "passive"))
      (node (ref "TRK2") (pin "4") (pinfunction "2.2_4") (pintype "passive"))
      (node (ref "TRK3") (pin "3") (pinfunction "2.1_3") (pintype "passive"))
      (node (ref "TRK3") (pin "4") (pinfunction "2.2_4") (pintype "passive"))
      (node (ref "TRK4") (pin "3") (pinfunction "2.1_3") (pintype "passive"))
      (node (ref "TRK4") (pin "4") (pinfunction "2.2_4") (pintype "passive"))
      (node (ref "TRK5") (pin "3") (pinfunction "2.1_3") (pintype "passive"))
      (node (ref "TRK5") (pin "4") (pinfunction "2.2_4") (pintype "passive"))
      (node (ref "TRK6") (pin "3") (pinfunction "2.1_3") (pintype "passive"))
      (node (ref "TRK6") (pin "4") (pinfunction "2.2_4") (pintype "passive"))
      (node (ref "W1") (pin "3") (pinfunction "2.1_3") (pintype "passive"))
      (node (ref "W1") (pin "4") (pinfunction "2.2_4") (pintype "passive"))
      (node (ref "W1011") (pin "3") (pinfunction "2.1_3") (pintype "passive"))
      (node (ref "W1011") (pin "4") (pinfunction "2.2_4") (pintype "passive"))
      (node (ref "W2A") (pin "3") (pinfunction "2.1_3") (pintype "passive"))
      (node (ref "W2A") (pin "4") (pinfunction "2.2_4") (pintype "passive"))
      (node (ref "W2B") (pin "3") (pinfunction "2.1_3") (pintype "passive"))
      (node (ref "W2B") (pin "4") (pinfunction "2.2_4") (pintype "passive"))
      (node (ref "W34") (pin "3") (pinfunction "2.1_3") (pintype "passive"))
      (node (ref "W34") (pin "4") (pinfunction "2.2_4") (pintype "passive"))
      (node (ref "W56") (pin "3") (pinfunction "2.1_3") (pintype "passive"))
      (node (ref "W56") (pin "4") (pinfunction "2.2_4") (pintype "passive"))
      (node (ref "W7A") (pin "3") (pinfunction "2.1_3") (pintype "passive"))
      (node (ref "W7A") (pin "4") (pinfunction "2.2_4") (pintype "passive"))
      (node (ref "W7B") (pin "3") (pinfunction "2.1_3") (pintype "passive"))
      (node (ref "W7B") (pin "4") (pinfunction "2.2_4") (pintype "passive"))
      (node (ref "W89") (pin "3") (pinfunction "2.1_3") (pintype "passive"))
      (node (ref "W89") (pin "4") (pinfunction "2.2_4") (pintype "passive"))
    )
    (net (code "19") (name "Net-(DLOCK-PadA)") (class "Default")
      (node (ref "DLOCK") (pin "A") (pinfunction "A_A") (pintype "passive"))
      (node (ref "R44") (pin "1") (pinfunction "1_1") (pintype "passive"))
    )
    (net (code "20") (name "Net-(DTRK1-PadA)") (class "Default")
      (node (ref "DTRK1") (pin "A") (pinfunction "A_A") (pintype "passive"))
      (node (ref "R32") (pin "1") (pinfunction "1_1") (pintype "passive"))
    )
    (net (code "21") (name "Net-(DTRK2-PadA)") (class "Default")
      (node (ref "DTRK2") (pin "A") (pinfunction "A_A") (pintype "passive"))
      (node (ref "R33") (pin "1") (pinfunction "1_1") (pintype "passive"))
    )
    (net (code "22") (name "Net-(DTRK3-PadA)") (class "Default")
      (node (ref "DTRK3") (pin "A") (pinfunction "A_A") (pintype "passive"))
      (node (ref "R36") (pin "1") (pinfunction "1_1") (pintype "passive"))
    )
    (net (code "23") (name "Net-(DTRK4-PadA)") (class "Default")
      (node (ref "DTRK4") (pin "A") (pinfunction "A_A") (pintype "passive"))
      (node (ref "R38") (pin "1") (pinfunction "1_1") (pintype "passive"))
    )
    (net (code "24") (name "Net-(DTRK5-PadA)") (class "Default")
      (node (ref "DTRK5") (pin "A") (pinfunction "A_A") (pintype "passive"))
      (node (ref "R40") (pin "1") (pinfunction "1_1") (pintype "passive"))
    )
    (net (code "25") (name "Net-(DTRK6-PadA)") (class "Default")
      (node (ref "DTRK6") (pin "A") (pinfunction "A_A") (pintype "passive"))
      (node (ref "R42") (pin "1") (pinfunction "1_1") (pintype "passive"))
    )
    (net (code "26") (name "Net-(DW1N-PadA)") (class "Default")
      (node (ref "DW1N") (pin "A") (pinfunction "A_A") (pintype "passive"))
      (node (ref "R1") (pin "1") (pinfunction "1_1") (pintype "passive"))
    )
    (net (code "27") (name "Net-(DW1R-PadA)") (class "Default")
      (node (ref "DW1R") (pin "A") (pinfunction "A_A") (pintype "passive"))
      (node (ref "R2") (pin "1") (pinfunction "1_1") (pintype "passive"))
    )
    (net (code "28") (name "Net-(DW2AN-PadA)") (class "Default")
      (node (ref "DW2AN") (pin "A") (pinfunction "A_A") (pintype "passive"))
      (node (ref "R4") (pin "1") (pinfunction "1_1") (pintype "passive"))
    )
    (net (code "29") (name "Net-(DW2AR-PadA)") (class "Default")
      (node (ref "DW2AR") (pin "A") (pinfunction "A_A") (pintype "passive"))
      (node (ref "R5") (pin "1") (pinfunction "1_1") (pintype "passive"))
    )
    (net (code "30") (name "Net-(DW2BN-PadA)") (class "Default")
      (node (ref "DW2BN") (pin "A") (pinfunction "A_A") (pintype "passive"))
      (node (ref "R7") (pin "1") (pinfunction "1_1") (pintype "passive"))
    )
    (net (code "31") (name "Net-(DW2BR-PadA)") (class "Default")
      (node (ref "DW2BR") (pin "A") (pinfunction "A_A") (pintype "passive"))
      (node (ref "R8") (pin "1") (pinfunction "1_1") (pintype "passive"))
    )
    (net (code "32") (name "Net-(DW7AN-PadA)") (class "Default")
      (node (ref "DW7AN") (pin "A") (pinfunction "A_A") (pintype "passive"))
      (node (ref "R18") (pin "1") (pinfunction "1_1") (pintype "passive"))
    )
    (net (code "33") (name "Net-(DW7AR-PadA)") (class "Default")
      (node (ref "DW7AR") (pin "A") (pinfunction "A_A") (pintype "passive"))
      (node (ref "R19") (pin "1") (pinfunction "1_1") (pintype "passive"))
    )
    (net (code "34") (name "Net-(DW7BN-PadA)") (class "Default")
      (node (ref "DW7BN") (pin "A") (pinfunction "A_A") (pintype "passive"))
      (node (ref "R21") (pin "1") (pinfunction "1_1") (pintype "passive"))
    )
    (net (code "35") (name "Net-(DW7BR-PadA)") (class "Default")
      (node (ref "DW7BR") (pin "A") (pinfunction "A_A") (pintype "passive"))
      (node (ref "R22") (pin "1") (pinfunction "1_1") (pintype "passive"))
    )
    (net (code "36") (name "Net-(DW34N-PadA)") (class "Default")
      (node (ref "DW34N") (pin "A") (pinfunction "A_A") (pintype "passive"))
      (node (ref "R10") (pin "1") (pinfunction "1_1") (pintype "passive"))
    )
    (net (code "37") (name "Net-(DW34N1-PadA)") (class "Default")
      (node (ref "DW34N1") (pin "A") (pinfunction "A_A") (pintype "passive"))
      (node (ref "R13") (pin "1") (pinfunction "1_1") (pintype "passive"))
    )
    (net (code "38") (name "Net-(DW34R-PadA)") (class "Default")
      (node (ref "DW34R") (pin "A") (pinfunction "A_A") (pintype "passive"))
      (node (ref "R11") (pin "1") (pinfunction "1_1") (pintype "passive"))
    )
    (net (code "39") (name "Net-(DW56N-PadA)") (class "Default")
      (node (ref "DW56N") (pin "A") (pinfunction "A_A") (pintype "passive"))
      (node (ref "R14") (pin "1") (pinfunction "1_1") (pintype "passive"))
    )
    (net (code "40") (name "Net-(DW56N1-PadA)") (class "Default")
      (node (ref "DW56N1") (pin "A") (pinfunction "A_A") (pintype "passive"))
      (node (ref "R17") (pin "1") (pinfunction "1_1") (pintype "passive"))
    )
    (net (code "41") (name "Net-(DW56R-PadA)") (class "Default")
      (node (ref "DW56R") (pin "A") (pinfunction "A_A") (pintype "passive"))
      (node (ref "R15") (pin "1") (pinfunction "1_1") (pintype "passive"))
    )
    (net (code "42") (name "Net-(DW89N-PadA)") (class "Default")
      (node (ref "DW89N") (pin "A") (pinfunction "A_A") (pintype "passive"))
      (node (ref "R24") (pin "1") (pinfunction "1_1") (pintype "passive"))
    )
    (net (code "43") (name "Net-(DW89N1-PadA)") (class "Default")
      (node (ref "DW89N1") (pin "A") (pinfunction "A_A") (pintype "passive"))
      (node (ref "R27") (pin "1") (pinfunction "1_1") (pintype "passive"))
    )
    (net (code "44") (name "Net-(DW89R-PadA)") (class "Default")
      (node (ref "DW89R") (pin "A") (pinfunction "A_A") (pintype "passive"))
      (node (ref "R25") (pin "1") (pinfunction "1_1") (pintype "passive"))
    )
    (net (code "45") (name "Net-(DW1011N-PadA)") (class "Default")
      (node (ref "DW1011N") (pin "A") (pinfunction "A_A") (pintype "passive"))
      (node (ref "R28") (pin "1") (pinfunction "1_1") (pintype "passive"))
    )
    (net (code "46") (name "Net-(DW1011N1-PadA)") (class "Default")
      (node (ref "DW1011N1") (pin "A") (pinfunction "A_A") (pintype "passive"))
      (node (ref "R31") (pin "1") (pinfunction "1_1") (pintype "passive"))
    )
    (net (code "47") (name "Net-(DW1011R-PadA)") (class "Default")
      (node (ref "DW1011R") (pin "A") (pinfunction "A_A") (pintype "passive"))
      (node (ref "R29") (pin "1") (pinfunction "1_1") (pintype "passive"))
    )
    (net (code "48") (name "Net-(LOCK-1.1)") (class "Default")
      (node (ref "LOCK") (pin "1") (pinfunction "1.1_1") (pintype "passive"))
      (node (ref "R45") (pin "2") (pinfunction "2_2") (pintype "passive"))
    )
    (net (code "49") (name "Net-(Q1-D)") (class "Default")
      (node (ref "DW1N") (pin "C") (pinfunction "C_C") (pintype "passive"))
      (node (ref "Q1") (pin "3") (pinfunction "D_3") (pintype "passive"))
    )
    (net (code "50") (name "Net-(Q2-D)") (class "Default")
      (node (ref "DW2AN") (pin "C") (pinfunction "C_C") (pintype "passive"))
      (node (ref "Q2") (pin "3") (pinfunction "D_3") (pintype "passive"))
    )
    (net (code "51") (name "Net-(Q3-D)") (class "Default")
      (node (ref "Q3") (pin "3") (pinfunction "D_3") (pintype "passive"))
      (node (ref "R2") (pin "2") (pinfunction "2_2") (pintype "passive"))
    )
    (net (code "52") (name "Net-(Q4-D)") (class "Default")
      (node (ref "Q4") (pin "3") (pinfunction "D_3") (pintype "passive"))
      (node (ref "R5") (pin "2") (pinfunction "2_2") (pintype "passive"))
    )
    (net (code "53") (name "Net-(Q5-D)") (class "Default")
      (node (ref "DW2BN") (pin "C") (pinfunction "C_C") (pintype "passive"))
      (node (ref "Q5") (pin "3") (pinfunction "D_3") (pintype "passive"))
    )
    (net (code "54") (name "Net-(Q6-D)") (class "Default")
      (node (ref "Q6") (pin "3") (pinfunction "D_3") (pintype "passive"))
      (node (ref "R8") (pin "2") (pinfunction "2_2") (pintype "passive"))
    )
    (net (code "55") (name "Net-(Q7-D)") (class "Default")
      (node (ref "DW34N") (pin "C") (pinfunction "C_C") (pintype "passive"))
      (node (ref "DW34N1") (pin "C") (pinfunction "C_C") (pintype "passive"))
      (node (ref "Q7") (pin "3") (pinfunction "D_3") (pintype "passive"))
    )
    (net (code "56") (name "Net-(Q8-D)") (class "Default")
      (node (ref "Q8") (pin "3") (pinfunction "D_3") (pintype "passive"))
      (node (ref "R11") (pin "2") (pinfunction "2_2") (pintype "passive"))
    )
    (net (code "57") (name "Net-(Q9-D)") (class "Default")
      (node (ref "DW56N") (pin "C") (pinfunction "C_C") (pintype "passive"))
      (node (ref "DW56N1") (pin "C") (pinfunction "C_C") (pintype "passive"))
      (node (ref "Q9") (pin "3") (pinfunction "D_3") (pintype "passive"))
    )
    (net (code "58") (name "Net-(Q10-D)") (class "Default")
      (node (ref "Q10") (pin "3") (pinfunction "D_3") (pintype "passive"))
      (node (ref "R15") (pin "2") (pinfunction "2_2") (pintype "passive"))
    )
    (net (code "59") (name "Net-(Q11-D)") (class "Default")
      (node (ref "DW7AN") (pin "C") (pinfunction "C_C") (pintype "passive"))
      (node (ref "Q11") (pin "3") (pinfunction "D_3") (pintype "passive"))
    )
    (net (code "60") (name "Net-(Q12-D)") (class "Default")
      (node (ref "Q12") (pin "3") (pinfunction "D_3") (pintype "passive"))
      (node (ref "R19") (pin "2") (pinfunction "2_2") (pintype "passive"))
    )
    (net (code "61") (name "Net-(Q13-D)") (class "Default")
      (node (ref "DW7BN") (pin "C") (pinfunction "C_C") (pintype "passive"))
      (node (ref "Q13") (pin "3") (pinfunction "D_3") (pintype "passive"))
    )
    (net (code "62") (name "Net-(Q14-D)") (class "Default")
      (node (ref "Q14") (pin "3") (pinfunction "D_3") (pintype "passive"))
      (node (ref "R22") (pin "2") (pinfunction "2_2") (pintype "passive"))
    )
    (net (code "63") (name "Net-(Q15-D)") (class "Default")
      (node (ref "DW89N") (pin "C") (pinfunction "C_C") (pintype "passive"))
      (node (ref "DW89N1") (pin "C") (pinfunction "C_C") (pintype "passive"))
      (node (ref "Q15") (pin "3") (pinfunction "D_3") (pintype "passive"))
    )
    (net (code "64") (name "Net-(Q16-D)") (class "Default")
      (node (ref "Q16") (pin "3") (pinfunction "D_3") (pintype "passive"))
      (node (ref "R25") (pin "2") (pinfunction "2_2") (pintype "passive"))
    )
    (net (code "65") (name "Net-(Q17-D)") (class "Default")
      (node (ref "DW1011N") (pin "C") (pinfunction "C_C") (pintype "passive"))
      (node (ref "DW1011N1") (pin "C") (pinfunction "C_C") (pintype "passive"))
      (node (ref "Q17") (pin "3") (pinfunction "D_3") (pintype "passive"))
    )
    (net (code "66") (name "Net-(Q18-D)") (class "Default")
      (node (ref "Q18") (pin "3") (pinfunction "D_3") (pintype "passive"))
      (node (ref "R29") (pin "2") (pinfunction "2_2") (pintype "passive"))
    )
    (net (code "67") (name "Net-(Q19-D)") (class "Default")
      (node (ref "DTRK1") (pin "C") (pinfunction "C_C") (pintype "passive"))
      (node (ref "Q19") (pin "3") (pinfunction "D_3") (pintype "passive"))
    )
    (net (code "68") (name "Net-(Q20-D)") (class "Default")
      (node (ref "DTRK2") (pin "C") (pinfunction "C_C") (pintype "passive"))
      (node (ref "Q20") (pin "3") (pinfunction "D_3") (pintype "passive"))
    )
    (net (code "69") (name "Net-(Q21-D)") (class "Default")
      (node (ref "DTRK3") (pin "C") (pinfunction "C_C") (pintype "passive"))
      (node (ref "Q21") (pin "3") (pinfunction "D_3") (pintype "passive"))
    )
    (net (code "70") (name "Net-(Q22-D)") (class "Default")
      (node (ref "DTRK4") (pin "C") (pinfunction "C_C") (pintype "passive"))
      (node (ref "Q22") (pin "3") (pinfunction "D_3") (pintype "passive"))
    )
    (net (code "71") (name "Net-(Q23-D)") (class "Default")
      (node (ref "DTRK5") (pin "C") (pinfunction "C_C") (pintype "passive"))
      (node (ref "Q23") (pin "3") (pinfunction "D_3") (pintype "passive"))
    )
    (net (code "72") (name "Net-(Q24-D)") (class "Default")
      (node (ref "DTRK6") (pin "C") (pinfunction "C_C") (pintype "passive"))
      (node (ref "Q24") (pin "3") (pinfunction "D_3") (pintype "passive"))
    )
    (net (code "73") (name "Net-(Q25-D)") (class "Default")
      (node (ref "DLOCK") (pin "C") (pinfunction "C_C") (pintype "passive"))
      (node (ref "Q25") (pin "3") (pinfunction "D_3") (pintype "passive"))
    )
    (net (code "74") (name "Net-(TRK1-1.1)") (class "Default")
      (node (ref "R34") (pin "2") (pinfunction "2_2") (pintype "passive"))
      (node (ref "TRK1") (pin "1") (pinfunction "1.1_1") (pintype "passive"))
    )
    (net (code "75") (name "Net-(TRK2-1.1)") (class "Default")
      (node (ref "R35") (pin "2") (pinfunction "2_2") (pintype "passive"))
      (node (ref "TRK2") (pin "1") (pinfunction "1.1_1") (pintype "passive"))
    )
    (net (code "76") (name "Net-(TRK3-1.1)") (class "Default")
      (node (ref "R37") (pin "2") (pinfunction "2_2") (pintype "passive"))
      (node (ref "TRK3") (pin "1") (pinfunction "1.1_1") (pintype "passive"))
    )
    (net (code "77") (name "Net-(TRK4-1.1)") (class "Default")
      (node (ref "R39") (pin "2") (pinfunction "2_2") (pintype "passive"))
      (node (ref "TRK4") (pin "1") (pinfunction "1.1_1") (pintype "passive"))
    )
    (net (code "78") (name "Net-(TRK5-1.1)") (class "Default")
      (node (ref "R41") (pin "2") (pinfunction "2_2") (pintype "passive"))
      (node (ref "TRK5") (pin "1") (pinfunction "1.1_1") (pintype "passive"))
    )
    (net (code "79") (name "Net-(TRK6-1.1)") (class "Default")
      (node (ref "R43") (pin "2") (pinfunction "2_2") (pintype "passive"))
      (node (ref "TRK6") (pin "1") (pinfunction "1.1_1") (pintype "passive"))
    )
    (net (code "80") (name "Net-(W1-1.1)") (class "Default")
      (node (ref "R3") (pin "2") (pinfunction "2_2") (pintype "passive"))
      (node (ref "W1") (pin "1") (pinfunction "1.1_1") (pintype "passive"))
    )
    (net (code "81") (name "Net-(W2A-1.1)") (class "Default")
      (node (ref "R6") (pin "2") (pinfunction "2_2") (pintype "passive"))
      (node (ref "W2A") (pin "1") (pinfunction "1.1_1") (pintype "passive"))
    )
    (net (code "82") (name "Net-(W2B-1.1)") (class "Default")
      (node (ref "R9") (pin "2") (pinfunction "2_2") (pintype "passive"))
      (node (ref "W2B") (pin "1") (pinfunction "1.1_1") (pintype "passive"))
    )
    (net (code "83") (name "Net-(W7A-1.1)") (class "Default")
      (node (ref "R20") (pin "2") (pinfunction "2_2") (pintype "passive"))
      (node (ref "W7A") (pin "1") (pinfunction "1.1_1") (pintype "passive"))
    )
    (net (code "84") (name "Net-(W7B-1.1)") (class "Default")
      (node (ref "R23") (pin "2") (pinfunction "2_2") (pintype "passive"))
      (node (ref "W7B") (pin "1") (pinfunction "1.1_1") (pintype "passive"))
    )
    (net (code "85") (name "Net-(W34-1.1)") (class "Default")
      (node (ref "R12") (pin "2") (pinfunction "2_2") (pintype "passive"))
      (node (ref "W34") (pin "1") (pinfunction "1.1_1") (pintype "passive"))
    )
    (net (code "86") (name "Net-(W56-1.1)") (class "Default")
      (node (ref "R16") (pin "2") (pinfunction "2_2") (pintype "passive"))
      (node (ref "W56") (pin "1") (pinfunction "1.1_1") (pintype "passive"))
    )
    (net (code "87") (name "Net-(W89-1.1)") (class "Default")
      (node (ref "R26") (pin "2") (pinfunction "2_2") (pintype "passive"))
      (node (ref "W89") (pin "1") (pinfunction "1.1_1") (pintype "passive"))
    )
    (net (code "88") (name "Net-(W1011-1.1)") (class "Default")
      (node (ref "R30") (pin "2") (pinfunction "2_2") (pintype "passive"))
      (node (ref "W1011") (pin "1") (pinfunction "1.1_1") (pintype "passive"))
    )
    (net (code "89") (name "unconnected-(LOCK-1.2-Pad2)") (class "Default")
      (node (ref "LOCK") (pin "2") (pinfunction "1.2_2") (pintype "passive"))
    )
    (net (code "90") (name "unconnected-(TRK1-1.2-Pad2)") (class "Default")
      (node (ref "TRK1") (pin "2") (pinfunction "1.2_2") (pintype "passive"))
    )
    (net (code "91") (name "unconnected-(TRK2-1.2-Pad2)") (class "Default")
      (node (ref "TRK2") (pin "2") (pinfunction "1.2_2") (pintype "passive"))
    )
    (net (code "92") (name "unconnected-(TRK3-1.2-Pad2)") (class "Default")
      (node (ref "TRK3") (pin "2") (pinfunction "1.2_2") (pintype "passive"))
    )
    (net (code "93") (name "unconnected-(TRK4-1.2-Pad2)") (class "Default")
      (node (ref "TRK4") (pin "2") (pinfunction "1.2_2") (pintype "passive"))
    )
    (net (code "94") (name "unconnected-(TRK5-1.2-Pad2)") (class "Default")
      (node (ref "TRK5") (pin "2") (pinfunction "1.2_2") (pintype "passive"))
    )
    (net (code "95") (name "unconnected-(TRK6-1.2-Pad2)") (class "Default")
      (node (ref "TRK6") (pin "2") (pinfunction "1.2_2") (pintype "passive"))
    )
    (net (code "96") (name "unconnected-(W1-1.2-Pad2)") (class "Default")
      (node (ref "W1") (pin "2") (pinfunction "1.2_2") (pintype "passive"))
    )
    (net (code "97") (name "unconnected-(W2A-1.2-Pad2)") (class "Default")
      (node (ref "W2A") (pin "2") (pinfunction "1.2_2") (pintype "passive"))
    )
    (net (code "98") (name "unconnected-(W2B-1.2-Pad2)") (class "Default")
      (node (ref "W2B") (pin "2") (pinfunction "1.2_2") (pintype "passive"))
    )
    (net (code "99") (name "unconnected-(W7A-1.2-Pad2)") (class "Default")
      (node (ref "W7A") (pin "2") (pinfunction "1.2_2") (pintype "passive"))
    )
    (net (code "100") (name "unconnected-(W7B-1.2-Pad2)") (class "Default")
      (node (ref "W7B") (pin "2") (pinfunction "1.2_2") (pintype "passive"))
    )
    (net (code "101") (name "unconnected-(W34-1.2-Pad2)") (class "Default")
      (node (ref "W34") (pin "2") (pinfunction "1.2_2") (pintype "passive"))
    )
    (net (code "102") (name "unconnected-(W56-1.2-Pad2)") (class "Default")
      (node (ref "W56") (pin "2") (pinfunction "1.2_2") (pintype "passive"))
    )
    (net (code "103") (name "unconnected-(W89-1.2-Pad2)") (class "Default")
      (node (ref "W89") (pin "2") (pinfunction "1.2_2") (pintype "passive"))
    )
    (net (code "104") (name "unconnected-(W1011-1.2-Pad2)") (class "Default")
      (node (ref "W1011") (pin "2") (pinfunction "1.2_2") (pintype "passive"))
    )
  )
)
